# Schematic.net
KiCad netlist of a schematic drawn in EAGLE
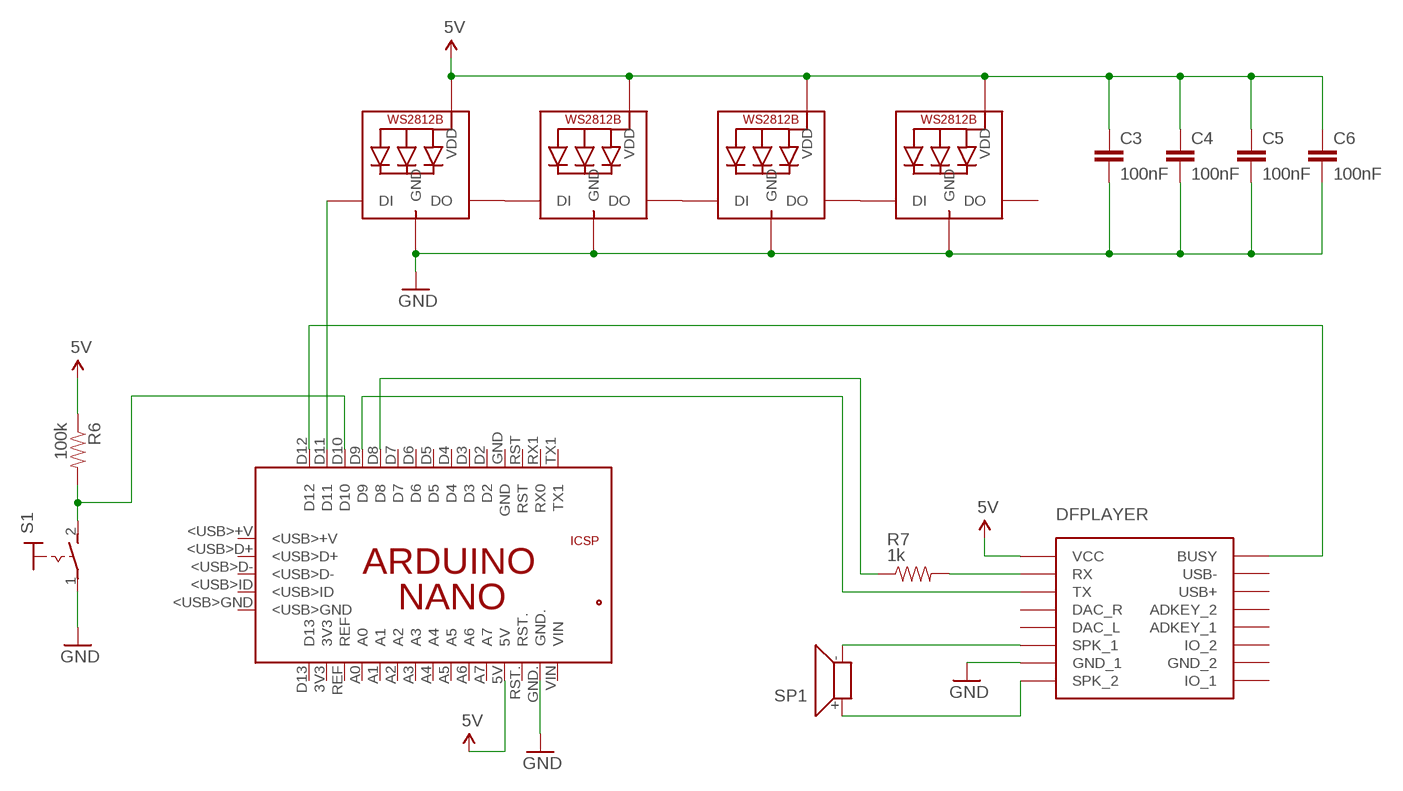
[diagram p0: schematic, sheet 1]

(export (version "E")
  (design (tool "Eeschema 10.0.6"))
  (components
    (comp (ref "C3")
      (value "100nF")
      (footprint "eagle-import:C102-054X133")
      (libsource (lib "eagle-import") (part "C-EU102-054X133"))
    )
    (comp (ref "C4")
      (value "100nF")
      (footprint "eagle-import:C102-054X133")
      (libsource (lib "eagle-import") (part "C-EU102-054X133"))
    )
    (comp (ref "C5")
      (value "100nF")
      (footprint "eagle-import:C102-054X133")
      (libsource (lib "eagle-import") (part "C-EU102-054X133"))
    )
    (comp (ref "C6")
      (value "100nF")
      (footprint "eagle-import:C102-054X133")
      (libsource (lib "eagle-import") (part "C-EU102-054X133"))
    )
    (comp (ref "LED1")
      (value "WS2812B3535")
      (footprint "eagle-import:LED3535")
      (libsource (lib "eagle-import") (part "WS2812B3535"))
    )
    (comp (ref "LED2")
      (value "WS2812B3535")
      (footprint "eagle-import:LED3535")
      (libsource (lib "eagle-import") (part "WS2812B3535"))
    )
    (comp (ref "LED3")
      (value "WS2812B3535")
      (footprint "eagle-import:LED3535")
      (libsource (lib "eagle-import") (part "WS2812B3535"))
    )
    (comp (ref "LED4")
      (value "WS2812B3535")
      (footprint "eagle-import:LED3535")
      (libsource (lib "eagle-import") (part "WS2812B3535"))
    )
    (comp (ref "PCB1")
      (value "ARDUINO_NANO")
      (footprint "eagle-import:ARDUINO_NANO")
      (libsource (lib "eagle-import") (part "ARDUINO_NANO"))
    )
    (comp (ref "R6")
      (value "100k")
      (footprint "eagle-import:0402-RES")
      (libsource (lib "eagle-import") (part "RESISTOR0402-RES"))
    )
    (comp (ref "R7")
      (value "1k")
      (footprint "eagle-import:0402-RES")
      (libsource (lib "eagle-import") (part "RESISTOR0402-RES"))
    )
    (comp (ref "S1")
      (value "MS243")
      (footprint "eagle-import:MS243")
      (libsource (lib "eagle-import") (part "MS243"))
    )
    (comp (ref "SP1")
      (value "SMS-1308MS-2-R")
      (footprint "eagle-import:SMS-1308MS-2-R")
      (libsource (lib "eagle-import") (part "SMS-1308MS-2-R"))
    )
    (comp (ref "U$8")
      (value "DF")
      (footprint "eagle-import:DFPLAYER")
      (libsource (lib "eagle-import") (part "DFPLAYER"))
    )
  )
  (nets
    (net (code "1") (name "5V") (class "Default")
      (node (ref "C3") (pin "1") (pinfunction "1_1") (pintype "passive"))
      (node (ref "C4") (pin "1") (pinfunction "1_1") (pintype "passive"))
      (node (ref "C5") (pin "1") (pinfunction "1_1") (pintype "passive"))
      (node (ref "C6") (pin "1") (pinfunction "1_1") (pintype "passive"))
      (node (ref "LED1") (pin "2") (pinfunction "VDD_2") (pintype "power_in"))
      (node (ref "LED2") (pin "2") (pinfunction "VDD_2") (pintype "power_in"))
      (node (ref "LED3") (pin "2") (pinfunction "VDD_2") (pintype "power_in"))
      (node (ref "LED4") (pin "2") (pinfunction "VDD_2") (pintype "power_in"))
      (node (ref "PCB1") (pin "5V") (pinfunction "5V_5V") (pintype "bidirectional"))
      (node (ref "R6") (pin "1") (pinfunction "1_1") (pintype "passive"))
      (node (ref "U$8") (pin "VCC") (pinfunction "VCC_VCC") (pintype "bidirectional"))
    )
    (net (code "2") (name "GND") (class "Default")
      (node (ref "C3") (pin "2") (pinfunction "2_2") (pintype "passive"))
      (node (ref "C4") (pin "2") (pinfunction "2_2") (pintype "passive"))
      (node (ref "C5") (pin "2") (pinfunction "2_2") (pintype "passive"))
      (node (ref "C6") (pin "2") (pinfunction "2_2") (pintype "passive"))
      (node (ref "LED1") (pin "4") (pinfunction "GND_4") (pintype "power_in"))
      (node (ref "LED2") (pin "4") (pinfunction "GND_4") (pintype "power_in"))
      (node (ref "LED3") (pin "4") (pinfunction "GND_4") (pintype "power_in"))
      (node (ref "LED4") (pin "4") (pinfunction "GND_4") (pintype "power_in"))
      (node (ref "PCB1") (pin "GND.") (pinfunction "GND._GND.") (pintype "bidirectional"))
      (node (ref "S1") (pin "1") (pinfunction "P_1") (pintype "passive"))
      (node (ref "U$8") (pin "GND_1") (pinfunction "GND_1_GND_1") (pintype "bidirectional"))
    )
    (net (code "3") (name "Net-(LED1-DI)") (class "Default")
      (node (ref "LED1") (pin "1") (pinfunction "DI_1") (pintype "input"))
      (node (ref "PCB1") (pin "D11") (pinfunction "D11_D11") (pintype "bidirectional"))
    )
    (net (code "4") (name "Net-(LED1-DO)") (class "Default")
      (node (ref "LED1") (pin "3") (pinfunction "DO_3") (pintype "output"))
      (node (ref "LED2") (pin "1") (pinfunction "DI_1") (pintype "input"))
    )
    (net (code "5") (name "Net-(LED2-DO)") (class "Default")
      (node (ref "LED2") (pin "3") (pinfunction "DO_3") (pintype "output"))
      (node (ref "LED3") (pin "1") (pinfunction "DI_1") (pintype "input"))
    )
    (net (code "6") (name "Net-(LED3-DO)") (class "Default")
      (node (ref "LED3") (pin "3") (pinfunction "DO_3") (pintype "output"))
      (node (ref "LED4") (pin "1") (pinfunction "DI_1") (pintype "input"))
    )
    (net (code "7") (name "Net-(PCB1-PadD8)") (class "Default")
      (node (ref "PCB1") (pin "D8") (pinfunction "D8_D8") (pintype "bidirectional"))
      (node (ref "R7") (pin "1") (pinfunction "1_1") (pintype "passive"))
    )
    (net (code "8") (name "Net-(PCB1-PadD9)") (class "Default")
      (node (ref "PCB1") (pin "D9") (pinfunction "D9_D9") (pintype "bidirectional"))
      (node (ref "U$8") (pin "TX") (pinfunction "TX_TX") (pintype "bidirectional"))
    )
    (net (code "9") (name "Net-(PCB1-PadD12)") (class "Default")
      (node (ref "PCB1") (pin "D12") (pinfunction "D12_D12") (pintype "bidirectional"))
      (node (ref "U$8") (pin "BUSY") (pinfunction "BUSY_BUSY") (pintype "bidirectional"))
    )
    (net (code "10") (name "Net-(R7-Pad2)") (class "Default")
      (node (ref "R7") (pin "2") (pinfunction "2_2") (pintype "passive"))
      (node (ref "U$8") (pin "RX") (pinfunction "RX_RX") (pintype "bidirectional"))
    )
    (net (code "11") (name "Net-(S1-S)") (class "Default")
      (node (ref "PCB1") (pin "D10") (pinfunction "D10_D10") (pintype "bidirectional"))
      (node (ref "R6") (pin "2") (pinfunction "2_2") (pintype "passive"))
      (node (ref "S1") (pin "2") (pinfunction "S_2") (pintype "passive"))
    )
    (net (code "12") (name "Net-(SP1-1)") (class "Default")
      (node (ref "SP1") (pin "+") (pinfunction "1_+") (pintype "passive"))
      (node (ref "U$8") (pin "SPK2") (pinfunction "SPK_2_SPK2") (pintype "bidirectional"))
    )
    (net (code "13") (name "Net-(SP1-2)") (class "Default")
      (node (ref "SP1") (pin "-") (pinfunction "2_-") (pintype "passive"))
      (node (ref "U$8") (pin "SPK1") (pinfunction "SPK_1_SPK1") (pintype "bidirectional"))
    )
    (net (code "14") (name "unconnected-(LED4-DO-Pad3)") (class "Default")
      (node (ref "LED4") (pin "3") (pinfunction "DO_3") (pintype "output"))
    )
    (net (code "15") (name "unconnected-(PCB1-Pad3V3)") (class "Default")
      (node (ref "PCB1") (pin "3V3") (pinfunction "3V3_3V3") (pintype "bidirectional"))
    )
    (net (code "16") (name "unconnected-(PCB1-Pad5V.)") (class "Default")
      (node (ref "PCB1") (pin "5V.") (pinfunction "5V._5V.") (pintype "bidirectional"))
    )
    (net (code "17") (name "unconnected-(PCB1-Pad<USB>+V)") (class "Default")
      (node (ref "PCB1") (pin "<USB>+V") (pinfunction "<USB>+V_<USB>+V") (pintype "bidirectional"))
    )
    (net (code "18") (name "unconnected-(PCB1-Pad<USB>D+)") (class "Default")
      (node (ref "PCB1") (pin "<USB>D+") (pinfunction "<USB>D+_<USB>D+") (pintype "bidirectional"))
    )
    (net (code "19") (name "unconnected-(PCB1-Pad<USB>D-)") (class "Default")
      (node (ref "PCB1") (pin "<USB>D-") (pinfunction "<USB>D-_<USB>D-") (pintype "bidirectional"))
    )
    (net (code "20") (name "unconnected-(PCB1-Pad<USB>GND)") (class "Default")
      (node (ref "PCB1") (pin "<USB>GND") (pinfunction "<USB>GND_<USB>GND") (pintype "bidirectional"))
    )
    (net (code "21") (name "unconnected-(PCB1-Pad<USB>ID)") (class "Default")
      (node (ref "PCB1") (pin "<USB>ID") (pinfunction "<USB>ID_<USB>ID") (pintype "bidirectional"))
    )
    (net (code "22") (name "unconnected-(PCB1-PadA0)") (class "Default")
      (node (ref "PCB1") (pin "A0") (pinfunction "A0_A0") (pintype "bidirectional"))
    )
    (net (code "23") (name "unconnected-(PCB1-PadA1)") (class "Default")
      (node (ref "PCB1") (pin "A1") (pinfunction "A1_A1") (pintype "bidirectional"))
    )
    (net (code "24") (name "unconnected-(PCB1-PadA2)") (class "Default")
      (node (ref "PCB1") (pin "A2") (pinfunction "A2_A2") (pintype "bidirectional"))
    )
    (net (code "25") (name "unconnected-(PCB1-PadA3)") (class "Default")
      (node (ref "PCB1") (pin "A3") (pinfunction "A3_A3") (pintype "bidirectional"))
    )
    (net (code "26") (name "unconnected-(PCB1-PadA4)") (class "Default")
      (node (ref "PCB1") (pin "A4") (pinfunction "A4_A4") (pintype "bidirectional"))
    )
    (net (code "27") (name "unconnected-(PCB1-PadA5)") (class "Default")
      (node (ref "PCB1") (pin "A5") (pinfunction "A5_A5") (pintype "bidirectional"))
    )
    (net (code "28") (name "unconnected-(PCB1-PadA6)") (class "Default")
      (node (ref "PCB1") (pin "A6") (pinfunction "A6_A6") (pintype "bidirectional"))
    )
    (net (code "29") (name "unconnected-(PCB1-PadA7)") (class "Default")
      (node (ref "PCB1") (pin "A7") (pinfunction "A7_A7") (pintype "bidirectional"))
    )
    (net (code "30") (name "unconnected-(PCB1-PadD2)") (class "Default")
      (node (ref "PCB1") (pin "D2") (pinfunction "D2_D2") (pintype "bidirectional"))
    )
    (net (code "31") (name "unconnected-(PCB1-PadD3)") (class "Default")
      (node (ref "PCB1") (pin "D3") (pinfunction "D3_D3") (pintype "bidirectional"))
    )
    (net (code "32") (name "unconnected-(PCB1-PadD4)") (class "Default")
      (node (ref "PCB1") (pin "D4") (pinfunction "D4_D4") (pintype "bidirectional"))
    )
    (net (code "33") (name "unconnected-(PCB1-PadD5)") (class "Default")
      (node (ref "PCB1") (pin "D5") (pinfunction "D5_D5") (pintype "bidirectional"))
    )
    (net (code "34") (name "unconnected-(PCB1-PadD6)") (class "Default")
      (node (ref "PCB1") (pin "D6") (pinfunction "D6_D6") (pintype "bidirectional"))
    )
    (net (code "35") (name "unconnected-(PCB1-PadD7)") (class "Default")
      (node (ref "PCB1") (pin "D7") (pinfunction "D7_D7") (pintype "bidirectional"))
    )
    (net (code "36") (name "unconnected-(PCB1-PadD13)") (class "Default")
      (node (ref "PCB1") (pin "D13") (pinfunction "D13_D13") (pintype "bidirectional"))
    )
    (net (code "37") (name "unconnected-(PCB1-PadGND)") (class "Default")
      (node (ref "PCB1") (pin "GND") (pinfunction "GND_GND") (pintype "bidirectional"))
    )
    (net (code "38") (name "unconnected-(PCB1-PadGND_)") (class "Default")
      (node (ref "PCB1") (pin "GND_") (pinfunction "GND__GND_") (pintype "bidirectional"))
    )
    (net (code "39") (name "unconnected-(PCB1-PadMISO)") (class "Default")
      (node (ref "PCB1") (pin "MISO") (pinfunction "MISO_MISO") (pintype "bidirectional"))
    )
    (net (code "40") (name "unconnected-(PCB1-PadMOSI)") (class "Default")
      (node (ref "PCB1") (pin "MOSI") (pinfunction "MOSI_MOSI") (pintype "bidirectional"))
    )
    (net (code "41") (name "unconnected-(PCB1-PadREF)") (class "Default")
      (node (ref "PCB1") (pin "REF") (pinfunction "REF_REF") (pintype "bidirectional"))
    )
    (net (code "42") (name "unconnected-(PCB1-PadRESET..)") (class "Default")
      (node (ref "PCB1") (pin "RESET..") (pinfunction "RESET.._RESET..") (pintype "bidirectional"))
    )
    (net (code "43") (name "unconnected-(PCB1-PadRST)") (class "Default")
      (node (ref "PCB1") (pin "RST") (pinfunction "RST_RST") (pintype "bidirectional"))
    )
    (net (code "44") (name "unconnected-(PCB1-PadRST.)") (class "Default")
      (node (ref "PCB1") (pin "RST.") (pinfunction "RST._RST.") (pintype "bidirectional"))
    )
    (net (code "45") (name "unconnected-(PCB1-PadSCK)") (class "Default")
      (node (ref "PCB1") (pin "SCK") (pinfunction "SCK_SCK") (pintype "bidirectional"))
    )
    (net (code "46") (name "unconnected-(PCB1-PadTX1)") (class "Default")
      (node (ref "PCB1") (pin "TX1") (pinfunction "TX1_TX1") (pintype "bidirectional"))
    )
    (net (code "47") (name "unconnected-(PCB1-PadVIN)") (class "Default")
      (node (ref "PCB1") (pin "VIN") (pinfunction "VIN_VIN") (pintype "bidirectional"))
    )
    (net (code "48") (name "unconnected-(PCB1-RX0-PadRX1)") (class "Default")
      (node (ref "PCB1") (pin "RX1") (pinfunction "RX0_RX1") (pintype "bidirectional"))
    )
    (net (code "49") (name "unconnected-(U$8-ADKEY_1-PadADKEY1)") (class "Default")
      (node (ref "U$8") (pin "ADKEY1") (pinfunction "ADKEY_1_ADKEY1") (pintype "bidirectional"))
    )
    (net (code "50") (name "unconnected-(U$8-ADKEY_2-PadADKEY2)") (class "Default")
      (node (ref "U$8") (pin "ADKEY2") (pinfunction "ADKEY_2_ADKEY2") (pintype "bidirectional"))
    )
    (net (code "51") (name "unconnected-(U$8-IO_1-PadIO1)") (class "Default")
      (node (ref "U$8") (pin "IO1") (pinfunction "IO_1_IO1") (pintype "bidirectional"))
    )
    (net (code "52") (name "unconnected-(U$8-IO_2-PadIO2)") (class "Default")
      (node (ref "U$8") (pin "IO2") (pinfunction "IO_2_IO2") (pintype "bidirectional"))
    )
    (net (code "53") (name "unconnected-(U$8-PadDAC_L)") (class "Default")
      (node (ref "U$8") (pin "DAC_L") (pinfunction "DAC_L_DAC_L") (pintype "bidirectional"))
    )
    (net (code "54") (name "unconnected-(U$8-PadDAC_R)") (class "Default")
      (node (ref "U$8") (pin "DAC_R") (pinfunction "DAC_R_DAC_R") (pintype "bidirectional"))
    )
    (net (code "55") (name "unconnected-(U$8-PadGND_2)") (class "Default")
      (node (ref "U$8") (pin "GND_2") (pinfunction "GND_2_GND_2") (pintype "bidirectional"))
    )
    (net (code "56") (name "unconnected-(U$8-PadUSB+)") (class "Default")
      (node (ref "U$8") (pin "USB+") (pinfunction "USB+_USB+") (pintype "bidirectional"))
    )
    (net (code "57") (name "unconnected-(U$8-PadUSB-)") (class "Default")
      (node (ref "U$8") (pin "USB-") (pinfunction "USB-_USB-") (pintype "bidirectional"))
    )
  )
)
